# macropad_synthplug.net
KiCad netlist of a schematic drawn in EAGLE
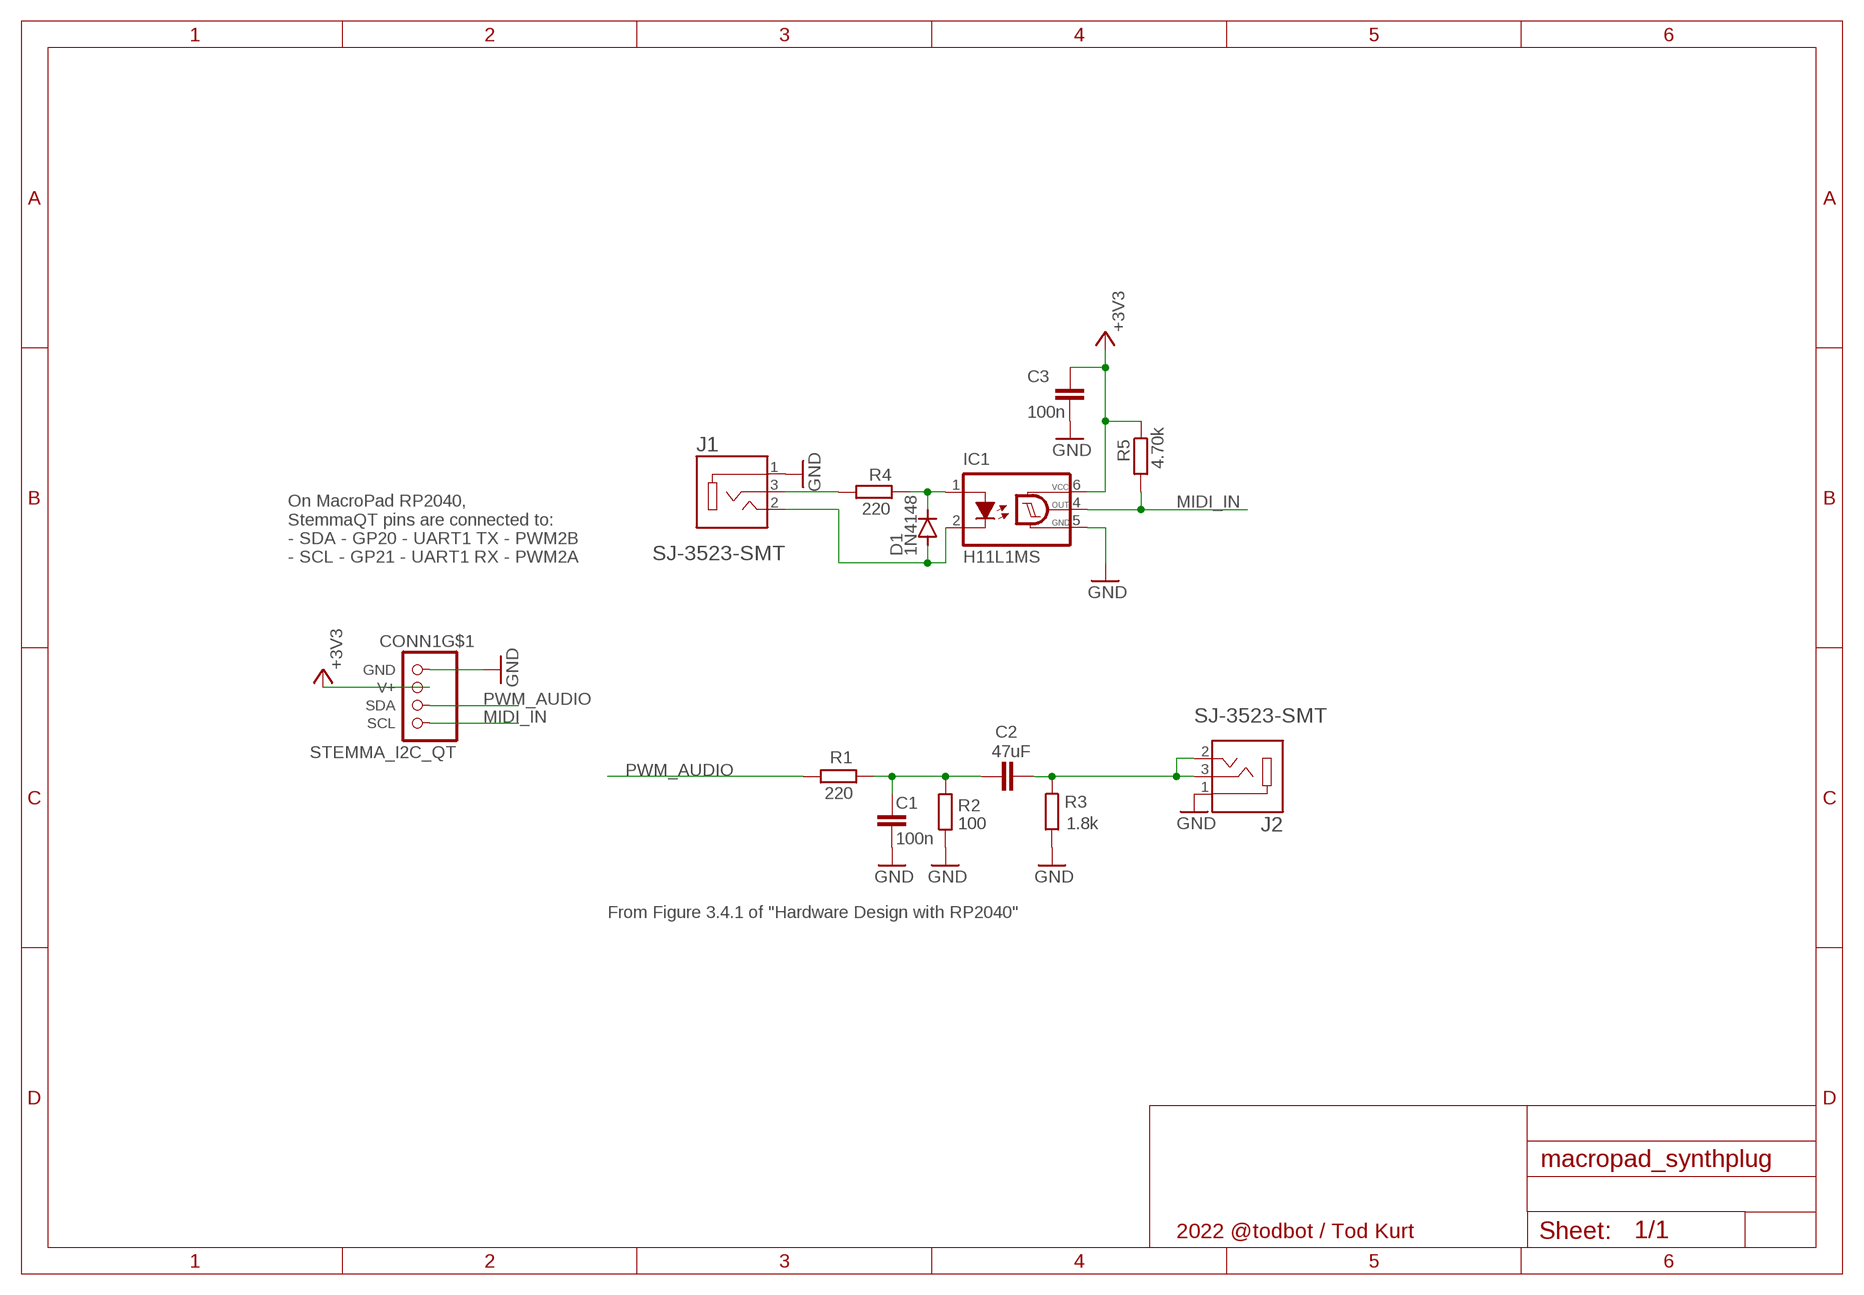
[diagram p0: schematic, sheet 1]

(export (version "E")
  (design (tool "Eeschema 10.0.6"))
  (components
    (comp (ref "C1")
      (value "100n")
      (footprint "eagle-import:C0805")
      (libsource (lib "eagle-import") (part "C-EUC0805"))
    )
    (comp (ref "C2")
      (value "47uF")
      (footprint "eagle-import:C0805")
      (libsource (lib "eagle-import") (part "C-EUC0805"))
    )
    (comp (ref "C3")
      (value "100n")
      (footprint "eagle-import:C0805")
      (libsource (lib "eagle-import") (part "C-EUC0805"))
    )
    (comp (ref "CONN1")
      (value "STEMMA_I2C_QT")
      (footprint "eagle-import:JST_SH4")
      (libsource (lib "eagle-import") (part "STEMMA_I2C_QT"))
    )
    (comp (ref "D1")
      (value "1N4148")
      (footprint "eagle-import:SOD123")
      (libsource (lib "eagle-import") (part "DIODE-SOD123"))
    )
    (comp (ref "IC1")
      (value "H11L1MS")
      (footprint "eagle-import:DIL6-SMD")
      (libsource (lib "eagle-import") (part "H11LMS1"))
    )
    (comp (ref "J1")
      (value "SJ-3523-SMT")
      (footprint "eagle-import:CUI_SJ-3523-SMT")
      (fields
        (field (name "DIGI-KEY_PART_NUMBER") "CP-3523SJCT-ND")
        (field (name "MF") "CUI Devices")
        (field (name "MP") "SJ-3523-SMT-TR")
      )
      (libsource (lib "eagle-import") (part "SJ-3523-SMT"))
    )
    (comp (ref "J2")
      (value "SJ-3523-SMT")
      (footprint "eagle-import:CUI_SJ-3523-SMT")
      (fields
        (field (name "DIGI-KEY_PART_NUMBER") "CP-3523SJCT-ND")
        (field (name "MF") "CUI Devices")
        (field (name "MP") "SJ-3523-SMT-TR")
      )
      (libsource (lib "eagle-import") (part "SJ-3523-SMT"))
    )
    (comp (ref "R1")
      (value "220")
      (footprint "eagle-import:R0805")
      (libsource (lib "eagle-import") (part "R-EU_R0805"))
    )
    (comp (ref "R2")
      (value "100")
      (footprint "eagle-import:R0805")
      (libsource (lib "eagle-import") (part "R-EU_R0805"))
    )
    (comp (ref "R3")
      (value "1.8k")
      (footprint "eagle-import:R0805")
      (libsource (lib "eagle-import") (part "R-EU_R0805"))
    )
    (comp (ref "R4")
      (value "220")
      (footprint "eagle-import:R0805")
      (libsource (lib "eagle-import") (part "R-EU_R0805"))
    )
    (comp (ref "R5")
      (value "4.70k")
      (footprint "eagle-import:R0805")
      (libsource (lib "eagle-import") (part "R-EU_R0805"))
    )
  )
  (nets
    (net (code "1") (name "+3V3") (class "Default")
      (node (ref "C3") (pin "1") (pinfunction "1_1") (pintype "passive"))
      (node (ref "CONN1") (pin "2") (pinfunction "V+_2") (pintype "passive"))
      (node (ref "IC1") (pin "6") (pinfunction "VCC_6") (pintype "power_in"))
      (node (ref "R5") (pin "1") (pinfunction "1_1") (pintype "passive"))
    )
    (net (code "2") (name "/MIDI_IN") (class "Default")
      (node (ref "CONN1") (pin "4") (pinfunction "SCL_4") (pintype "passive"))
      (node (ref "IC1") (pin "4") (pinfunction "OUT_4") (pintype "output"))
      (node (ref "R5") (pin "2") (pinfunction "2_2") (pintype "passive"))
    )
    (net (code "3") (name "/PWM_AUDIO") (class "Default")
      (node (ref "CONN1") (pin "3") (pinfunction "SDA_3") (pintype "passive"))
      (node (ref "R1") (pin "2") (pinfunction "2_2") (pintype "passive"))
    )
    (net (code "4") (name "GND") (class "Default")
      (node (ref "C1") (pin "2") (pinfunction "2_2") (pintype "passive"))
      (node (ref "C3") (pin "2") (pinfunction "2_2") (pintype "passive"))
      (node (ref "CONN1") (pin "1") (pinfunction "GND_1") (pintype "passive"))
      (node (ref "IC1") (pin "5") (pinfunction "GND_5") (pintype "power_in"))
      (node (ref "J1") (pin "1") (pinfunction "1_1") (pintype "passive"))
      (node (ref "J2") (pin "1") (pinfunction "1_1") (pintype "passive"))
      (node (ref "R2") (pin "1") (pinfunction "1_1") (pintype "passive"))
      (node (ref "R3") (pin "2") (pinfunction "2_2") (pintype "passive"))
    )
    (net (code "5") (name "Net-(C1-Pad1)") (class "Default")
      (node (ref "C1") (pin "1") (pinfunction "1_1") (pintype "passive"))
      (node (ref "C2") (pin "1") (pinfunction "1_1") (pintype "passive"))
      (node (ref "R1") (pin "1") (pinfunction "1_1") (pintype "passive"))
      (node (ref "R2") (pin "2") (pinfunction "2_2") (pintype "passive"))
    )
    (net (code "6") (name "Net-(C2-Pad2)") (class "Default")
      (node (ref "C2") (pin "2") (pinfunction "2_2") (pintype "passive"))
      (node (ref "J2") (pin "2") (pinfunction "2_2") (pintype "passive"))
      (node (ref "J2") (pin "3") (pinfunction "3_3") (pintype "passive"))
      (node (ref "R3") (pin "1") (pinfunction "1_1") (pintype "passive"))
    )
    (net (code "7") (name "Net-(IC1-A)") (class "Default")
      (node (ref "D1") (pin "C") (pinfunction "C_C") (pintype "passive"))
      (node (ref "IC1") (pin "1") (pinfunction "A_1") (pintype "passive"))
      (node (ref "R4") (pin "1") (pinfunction "1_1") (pintype "passive"))
    )
    (net (code "8") (name "Net-(IC1-C)") (class "Default")
      (node (ref "D1") (pin "A") (pinfunction "A_A") (pintype "passive"))
      (node (ref "IC1") (pin "2") (pinfunction "C_2") (pintype "passive"))
      (node (ref "J1") (pin "2") (pinfunction "2_2") (pintype "passive"))
    )
    (net (code "9") (name "Net-(J1-Pad3)") (class "Default")
      (node (ref "J1") (pin "3") (pinfunction "3_3") (pintype "passive"))
      (node (ref "R4") (pin "2") (pinfunction "2_2") (pintype "passive"))
    )
  )
)
